# Program_Counter.net
KiCad netlist of a schematic drawn in Altium Designer
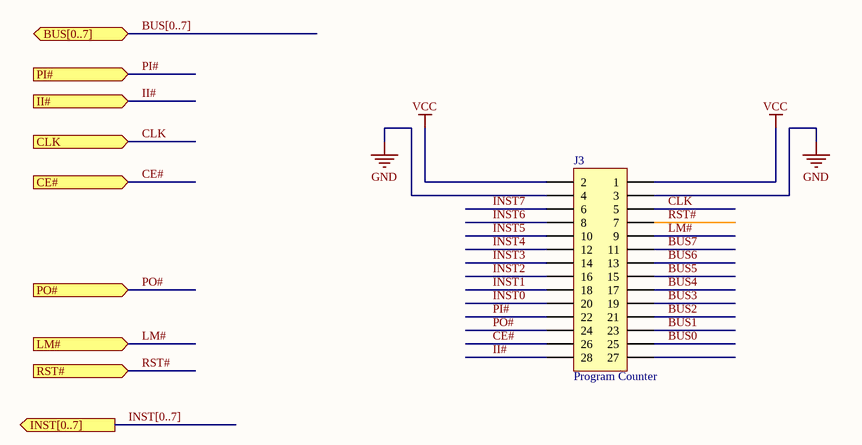
[diagram p0: Program Counter.SchDoc]

(export (version "E")
  (design (tool "Eeschema 10.0.6"))
  (components
    (comp (ref "J3")
      (value "Program Counter")
      (footprint "HDR2X14")
      (description "Header, 14-Pin, Dual row")
      (fields (field (name "PUBLISHER") "Altium Limited"))
      (libsource (lib "Miscellaneous Connectors") (part "Header 14X2"))
    )
  )
  (nets
    (net (code "1") (name "/BUS0") (class "Default")
      (node (ref "J3") (pin "25") (pinfunction "25_25") (pintype "passive"))
    )
    (net (code "2") (name "/BUS1") (class "Default")
      (node (ref "J3") (pin "23") (pinfunction "23_23") (pintype "passive"))
    )
    (net (code "3") (name "/BUS2") (class "Default")
      (node (ref "J3") (pin "21") (pinfunction "21_21") (pintype "passive"))
    )
    (net (code "4") (name "/BUS3") (class "Default")
      (node (ref "J3") (pin "19") (pinfunction "19_19") (pintype "passive"))
    )
    (net (code "5") (name "/BUS4") (class "Default")
      (node (ref "J3") (pin "17") (pinfunction "17_17") (pintype "passive"))
    )
    (net (code "6") (name "/BUS5") (class "Default")
      (node (ref "J3") (pin "15") (pinfunction "15_15") (pintype "passive"))
    )
    (net (code "7") (name "/BUS6") (class "Default")
      (node (ref "J3") (pin "13") (pinfunction "13_13") (pintype "passive"))
    )
    (net (code "8") (name "/BUS7") (class "Default")
      (node (ref "J3") (pin "11") (pinfunction "11_11") (pintype "passive"))
    )
    (net (code "10") (name "/CE#") (class "Default")
      (node (ref "J3") (pin "26") (pinfunction "26_26") (pintype "passive"))
    )
    (net (code "11") (name "/CLK") (class "Default")
      (node (ref "J3") (pin "5") (pinfunction "5_5") (pintype "passive"))
    )
    (net (code "12") (name "/II#") (class "Default")
      (node (ref "J3") (pin "28") (pinfunction "28_28") (pintype "passive"))
    )
    (net (code "13") (name "/INST0") (class "Default")
      (node (ref "J3") (pin "20") (pinfunction "20_20") (pintype "passive"))
    )
    (net (code "14") (name "/INST1") (class "Default")
      (node (ref "J3") (pin "18") (pinfunction "18_18") (pintype "passive"))
    )
    (net (code "15") (name "/INST2") (class "Default")
      (node (ref "J3") (pin "16") (pinfunction "16_16") (pintype "passive"))
    )
    (net (code "16") (name "/INST3") (class "Default")
      (node (ref "J3") (pin "14") (pinfunction "14_14") (pintype "passive"))
    )
    (net (code "17") (name "/INST4") (class "Default")
      (node (ref "J3") (pin "12") (pinfunction "12_12") (pintype "passive"))
    )
    (net (code "18") (name "/INST5") (class "Default")
      (node (ref "J3") (pin "10") (pinfunction "10_10") (pintype "passive"))
    )
    (net (code "19") (name "/INST6") (class "Default")
      (node (ref "J3") (pin "8") (pinfunction "8_8") (pintype "passive"))
    )
    (net (code "20") (name "/INST7") (class "Default")
      (node (ref "J3") (pin "6") (pinfunction "6_6") (pintype "passive"))
    )
    (net (code "22") (name "/LM#") (class "Default")
      (node (ref "J3") (pin "9") (pinfunction "9_9") (pintype "passive"))
    )
    (net (code "23") (name "/PI#") (class "Default")
      (node (ref "J3") (pin "22") (pinfunction "22_22") (pintype "passive"))
    )
    (net (code "24") (name "/PO#") (class "Default")
      (node (ref "J3") (pin "24") (pinfunction "24_24") (pintype "passive"))
    )
    (net (code "25") (name "/RST#") (class "Default")
      (node (ref "J3") (pin "7") (pinfunction "7_7") (pintype "passive"))
    )
    (net (code "26") (name "GND") (class "Default")
      (node (ref "J3") (pin "3") (pinfunction "3_3") (pintype "passive"))
      (node (ref "J3") (pin "4") (pinfunction "4_4") (pintype "passive"))
    )
    (net (code "27") (name "VCC") (class "Default")
      (node (ref "J3") (pin "1") (pinfunction "1_1") (pintype "passive"))
      (node (ref "J3") (pin "2") (pinfunction "2_2") (pintype "passive"))
    )
    (net (code "28") (name "unconnected-(J3-Pad27)") (class "Default")
      (node (ref "J3") (pin "27") (pinfunction "27_27") (pintype "passive"))
    )
  )
)
